# IMU_board_rev2.net
KiCad netlist of a schematic drawn in Altium Designer
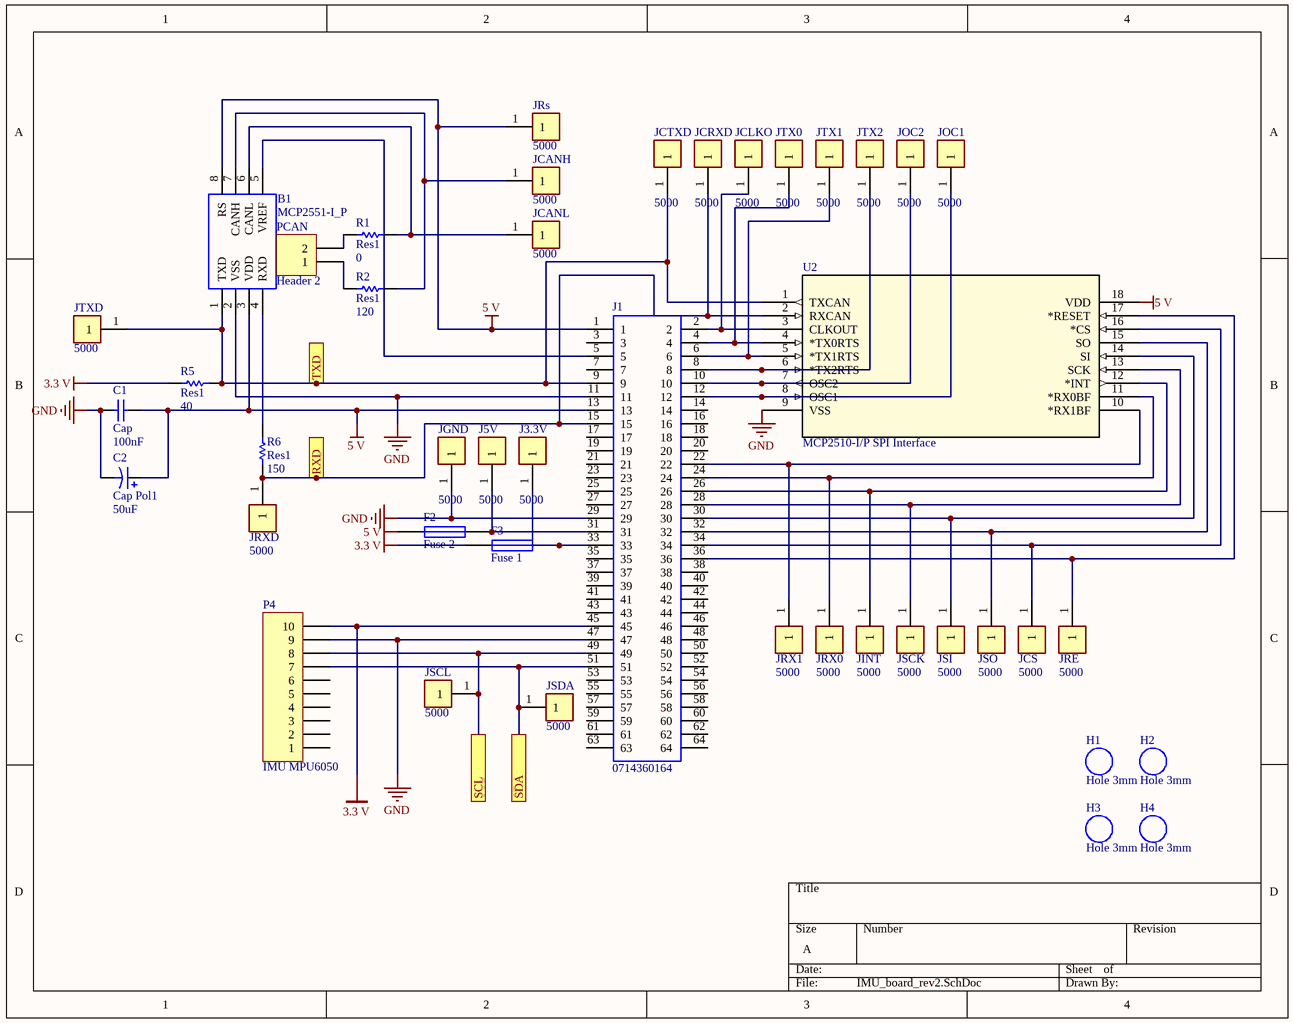
[diagram p0: IMU_board_rev2.SchDoc]

(export (version "E")
  (design (tool "Eeschema 10.0.6"))
  (components
    (comp (ref "B1")
      (value "MCP2551-I_P")
      (footprint "DIP794W56P254L946H432Q8N")
      (fields
        (field (name "MANUFACTURER_PART_NUMBER") "MCP2551-I/P")
        (field (name "MOUSER PART NUMBER") "579-MCP2551-I/P")
      )
      (libsource (lib "MCP2551-I_P") (part "MCP2551-I_P"))
    )
    (comp (ref "C1")
      (value "Cap")
      (footprint "Cap Pol")
      (description "Capacitor")
      (fields (field (name "ALTIUM_VALUE") "100nF") (field (name "PUBLISHER") "Altium Limited"))
      (libsource (lib "Miscellaneous Devices") (part "Cap"))
    )
    (comp (ref "C2")
      (value "Cap Pol1")
      (footprint "Cap Pol")
      (description "Polarized Capacitor (Radial)")
      (fields (field (name "ALTIUM_VALUE") "50uF") (field (name "PUBLISHER") "Altium Limited"))
      (libsource (lib "Miscellaneous Devices") (part "Cap Pol1"))
    )
    (comp (ref "F2")
      (value "Fuse 2")
      (footprint "PIN-W2/E2.8")
      (description "Fuse")
      (fields (field (name "PUBLISHER") "Altium Limited"))
      (libsource (lib "Miscellaneous Devices") (part "Fuse 1"))
    )
    (comp (ref "F3")
      (value "Fuse 1")
      (footprint "PIN-W2/E2.8")
      (description "Fuse")
      (fields (field (name "PUBLISHER") "Altium Limited"))
      (libsource (lib "Miscellaneous Devices") (part "Fuse 1"))
    )
    (comp (ref "H1")
      (value "Hole 3mm")
      (footprint "Hole 3mm")
      (libsource (lib "ECE LIB new") (part "Hole 3mm"))
    )
    (comp (ref "H2")
      (value "Hole 3mm")
      (footprint "Hole 3mm")
      (libsource (lib "ECE LIB new") (part "Hole 3mm"))
    )
    (comp (ref "H3")
      (value "Hole 3mm")
      (footprint "Hole 3mm")
      (libsource (lib "ECE LIB new") (part "Hole 3mm"))
    )
    (comp (ref "H4")
      (value "Hole 3mm")
      (footprint "Hole 3mm")
      (libsource (lib "ECE LIB new") (part "Hole 3mm"))
    )
    (comp (ref "J1")
      (value "0714360164")
      (footprint "0714360164")
      (description "Board to Board & Mezzanine Connectors 1.00MM PLG 02X32P VT SMT")
      (libsource (lib "0714360164") (part "0714360164"))
    )
    (comp (ref "J3.3V")
      (value "5000")
      (footprint "KEYSTONE_5000")
      (fields (field (name "MF") "Keystone"))
      (libsource (lib "5000") (part "5000"))
    )
    (comp (ref "J5V")
      (value "5000")
      (footprint "KEYSTONE_5000")
      (fields (field (name "MF") "Keystone"))
      (libsource (lib "5000") (part "5000"))
    )
    (comp (ref "JCANH")
      (value "5000")
      (footprint "KEYSTONE_5000")
      (fields (field (name "MF") "Keystone"))
      (libsource (lib "") (part "5000_2"))
    )
    (comp (ref "JCANL")
      (value "5000")
      (footprint "KEYSTONE_5000")
      (fields (field (name "MF") "Keystone"))
      (libsource (lib "") (part "5000_2"))
    )
    (comp (ref "JCLKO")
      (value "5000")
      (footprint "KEYSTONE_5000")
      (fields (field (name "MF") "Keystone"))
      (libsource (lib "5000") (part "5000"))
    )
    (comp (ref "JCRXD")
      (value "5000")
      (footprint "KEYSTONE_5000")
      (fields (field (name "MF") "Keystone"))
      (libsource (lib "5000") (part "5000"))
    )
    (comp (ref "JCS")
      (value "5000")
      (footprint "KEYSTONE_5000")
      (fields (field (name "MF") "Keystone"))
      (libsource (lib "") (part "5000_1"))
    )
    (comp (ref "JCTXD")
      (value "5000")
      (footprint "KEYSTONE_5000")
      (fields (field (name "MF") "Keystone"))
      (libsource (lib "5000") (part "5000"))
    )
    (comp (ref "JGND")
      (value "5000")
      (footprint "KEYSTONE_5000")
      (fields (field (name "MF") "Keystone"))
      (libsource (lib "5000") (part "5000"))
    )
    (comp (ref "JINT")
      (value "5000")
      (footprint "KEYSTONE_5000")
      (fields (field (name "MF") "Keystone"))
      (libsource (lib "") (part "5000_1"))
    )
    (comp (ref "JOC1")
      (value "5000")
      (footprint "KEYSTONE_5000")
      (fields (field (name "MF") "Keystone"))
      (libsource (lib "5000") (part "5000"))
    )
    (comp (ref "JOC2")
      (value "5000")
      (footprint "KEYSTONE_5000")
      (fields (field (name "MF") "Keystone"))
      (libsource (lib "5000") (part "5000"))
    )
    (comp (ref "JRE")
      (value "5000")
      (footprint "KEYSTONE_5000")
      (fields (field (name "MF") "Keystone"))
      (libsource (lib "") (part "5000_1"))
    )
    (comp (ref "JRs")
      (value "5000")
      (footprint "KEYSTONE_5000")
      (fields (field (name "MF") "Keystone"))
      (libsource (lib "") (part "5000_2"))
    )
    (comp (ref "JRX0")
      (value "5000")
      (footprint "KEYSTONE_5000")
      (fields (field (name "MF") "Keystone"))
      (libsource (lib "") (part "5000_1"))
    )
    (comp (ref "JRX1")
      (value "5000")
      (footprint "KEYSTONE_5000")
      (fields (field (name "MF") "Keystone"))
      (libsource (lib "") (part "5000_1"))
    )
    (comp (ref "JRXD")
      (value "5000")
      (footprint "KEYSTONE_5000")
      (fields (field (name "MF") "Keystone"))
      (libsource (lib "") (part "5000_1"))
    )
    (comp (ref "JSCK")
      (value "5000")
      (footprint "KEYSTONE_5000")
      (fields (field (name "MF") "Keystone"))
      (libsource (lib "") (part "5000_1"))
    )
    (comp (ref "JSCL")
      (value "5000")
      (footprint "KEYSTONE_5000")
      (fields (field (name "MF") "Keystone"))
      (libsource (lib "") (part "5000_3"))
    )
    (comp (ref "JSDA")
      (value "5000")
      (footprint "KEYSTONE_5000")
      (fields (field (name "MF") "Keystone"))
      (libsource (lib "") (part "5000_2"))
    )
    (comp (ref "JSI")
      (value "5000")
      (footprint "KEYSTONE_5000")
      (fields (field (name "MF") "Keystone"))
      (libsource (lib "") (part "5000_1"))
    )
    (comp (ref "JSO")
      (value "5000")
      (footprint "KEYSTONE_5000")
      (fields (field (name "MF") "Keystone"))
      (libsource (lib "") (part "5000_1"))
    )
    (comp (ref "JTX0")
      (value "5000")
      (footprint "KEYSTONE_5000")
      (fields (field (name "MF") "Keystone"))
      (libsource (lib "5000") (part "5000"))
    )
    (comp (ref "JTX1")
      (value "5000")
      (footprint "KEYSTONE_5000")
      (fields (field (name "MF") "Keystone"))
      (libsource (lib "5000") (part "5000"))
    )
    (comp (ref "JTX2")
      (value "5000")
      (footprint "KEYSTONE_5000")
      (fields (field (name "MF") "Keystone"))
      (libsource (lib "5000") (part "5000"))
    )
    (comp (ref "JTXD")
      (value "5000")
      (footprint "KEYSTONE_5000")
      (fields (field (name "MF") "Keystone"))
      (libsource (lib "") (part "5000_3"))
    )
    (comp (ref "P4")
      (value "IMU MPU6050")
      (footprint "HDR1X10")
      (description "Header, 10-Pin")
      (fields (field (name "PUBLISHER") "Altium Limited"))
      (libsource (lib "Miscellaneous Connectors") (part "Header 10"))
    )
    (comp (ref "PCAN")
      (value "Header 2")
      (footprint "HDR1X2")
      (description "Header, 2-Pin")
      (fields (field (name "PUBLISHER") "Altium Limited"))
      (libsource (lib "Miscellaneous Connectors") (part "Header 2"))
    )
    (comp (ref "R1")
      (value "Res1")
      (footprint "AXIAL-0.3")
      (description "Resistor")
      (fields (field (name "ALTIUM_VALUE") "0") (field (name "PUBLISHER") "Altium Limited"))
      (libsource (lib "Miscellaneous Devices") (part "Res1"))
    )
    (comp (ref "R2")
      (value "Res1")
      (footprint "AXIAL-0.3")
      (description "Resistor")
      (fields (field (name "ALTIUM_VALUE") "120") (field (name "PUBLISHER") "Altium Limited"))
      (libsource (lib "Miscellaneous Devices") (part "Res1"))
    )
    (comp (ref "R5")
      (value "Res1")
      (footprint "AXIAL-0.3")
      (description "Resistor")
      (fields (field (name "ALTIUM_VALUE") "40") (field (name "PUBLISHER") "Altium Limited"))
      (libsource (lib "Miscellaneous Devices") (part "Res1"))
    )
    (comp (ref "R6")
      (value "Res1")
      (footprint "AXIAL-0.3")
      (description "Resistor")
      (fields (field (name "ALTIUM_VALUE") "150") (field (name "PUBLISHER") "Altium Limited"))
      (libsource (lib "Miscellaneous Devices") (part "Res1"))
    )
    (comp (ref "U2")
      (value "MCP2510-I/P SPI Interface")
      (footprint "PDIP18_300MC_MCH")
      (description "No Description Available")
      (fields
        (field (name "MANUFACTURER_PART_NUMBER") "MCP2510-I/P")
        (field (name "COPYRIGHT") "Copyright (C) 2022 Ultra Librarian. All rights reserved.")
      )
      (libsource (lib "MCP2510-I&slash_P") (part "MCP2510-I/P"))
    )
  )
  (nets
    (net (code "1") (name "/RXD") (class "Default")
      (node (ref "J1") (pin "15") (pinfunction "15_15") (pintype "passive"))
      (node (ref "JCRXD") (pin "1") (pinfunction "1_1") (pintype "passive"))
      (node (ref "JRXD") (pin "1") (pinfunction "1_1") (pintype "passive"))
      (node (ref "R6") (pin "2") (pinfunction "2_2") (pintype "passive"))
      (node (ref "U2") (pin "2") (pinfunction "RXCAN_2") (pintype "input"))
    )
    (net (code "2") (name "/SCL") (class "Default")
      (node (ref "J1") (pin "49") (pinfunction "49_49") (pintype "passive"))
      (node (ref "JSCL") (pin "1") (pinfunction "1_1") (pintype "passive"))
      (node (ref "P4") (pin "8") (pinfunction "8_8") (pintype "passive"))
    )
    (net (code "3") (name "/SDA") (class "Default")
      (node (ref "J1") (pin "51") (pinfunction "51_51") (pintype "passive"))
      (node (ref "JSDA") (pin "1") (pinfunction "1_1") (pintype "passive"))
      (node (ref "P4") (pin "7") (pinfunction "7_7") (pintype "passive"))
    )
    (net (code "4") (name "/TXD") (class "Default")
      (node (ref "B1") (pin "1") (pinfunction "TXD_1") (pintype "passive"))
      (node (ref "J1") (pin "9") (pinfunction "9_9") (pintype "passive"))
      (node (ref "JCTXD") (pin "1") (pinfunction "1_1") (pintype "passive"))
      (node (ref "JTXD") (pin "1") (pinfunction "1_1") (pintype "passive"))
      (node (ref "R5") (pin "1") (pinfunction "1_1") (pintype "passive"))
      (node (ref "U2") (pin "1") (pinfunction "TXCAN_1") (pintype "output"))
    )
    (net (code "5") (name "3.3 V") (class "Default")
      (node (ref "F3") (pin "2") (pinfunction "2_2") (pintype "passive"))
      (node (ref "J1") (pin "45") (pinfunction "45_45") (pintype "passive"))
      (node (ref "P4") (pin "10") (pinfunction "10_10") (pintype "passive"))
      (node (ref "R5") (pin "2") (pinfunction "2_2") (pintype "passive"))
    )
    (net (code "6") (name "5 V") (class "Default")
      (node (ref "B1") (pin "3") (pinfunction "VDD_3") (pintype "passive"))
      (node (ref "B1") (pin "8") (pinfunction "RS_8") (pintype "passive"))
      (node (ref "C1") (pin "2") (pinfunction "2_2") (pintype "passive"))
      (node (ref "C2") (pin "1") (pinfunction "1_1") (pintype "passive"))
      (node (ref "F2") (pin "2") (pinfunction "2_2") (pintype "passive"))
      (node (ref "J1") (pin "1") (pinfunction "1_1") (pintype "passive"))
      (node (ref "J1") (pin "13") (pinfunction "13_13") (pintype "passive"))
      (node (ref "JRs") (pin "1") (pinfunction "1_1") (pintype "passive"))
      (node (ref "U2") (pin "18") (pinfunction "VDD_18") (pintype "passive"))
    )
    (net (code "7") (name "GND") (class "Default")
      (node (ref "B1") (pin "2") (pinfunction "VSS_2") (pintype "passive"))
      (node (ref "C1") (pin "1") (pinfunction "1_1") (pintype "passive"))
      (node (ref "C2") (pin "2") (pinfunction "2_2") (pintype "passive"))
      (node (ref "J1") (pin "11") (pinfunction "11_11") (pintype "passive"))
      (node (ref "J1") (pin "29") (pinfunction "29_29") (pintype "passive"))
      (node (ref "J1") (pin "47") (pinfunction "47_47") (pintype "passive"))
      (node (ref "JGND") (pin "1") (pinfunction "1_1") (pintype "passive"))
      (node (ref "P4") (pin "9") (pinfunction "9_9") (pintype "passive"))
      (node (ref "U2") (pin "9") (pinfunction "VSS_9") (pintype "passive"))
    )
    (net (code "8") (name "Net-(B1-CANH)") (class "Default")
      (node (ref "B1") (pin "7") (pinfunction "CANH_7") (pintype "passive"))
      (node (ref "JCANH") (pin "1") (pinfunction "1_1") (pintype "passive"))
      (node (ref "R2") (pin "2") (pinfunction "2_2") (pintype "passive"))
    )
    (net (code "9") (name "Net-(B1-CANL)") (class "Default")
      (node (ref "B1") (pin "6") (pinfunction "CANL_6") (pintype "passive"))
      (node (ref "JCANL") (pin "1") (pinfunction "1_1") (pintype "passive"))
      (node (ref "R1") (pin "2") (pinfunction "2_2") (pintype "passive"))
    )
    (net (code "10") (name "Net-(B1-RXD)") (class "Default")
      (node (ref "B1") (pin "4") (pinfunction "RXD_4") (pintype "passive"))
      (node (ref "R6") (pin "1") (pinfunction "1_1") (pintype "passive"))
    )
    (net (code "11") (name "Net-(B1-VREF)") (class "Default")
      (node (ref "B1") (pin "5") (pinfunction "VREF_5") (pintype "passive"))
      (node (ref "J1") (pin "5") (pinfunction "5_5") (pintype "passive"))
    )
    (net (code "12") (name "Net-(F2-Pad1)") (class "Default")
      (node (ref "F2") (pin "1") (pinfunction "1_1") (pintype "passive"))
      (node (ref "J1") (pin "31") (pinfunction "31_31") (pintype "passive"))
      (node (ref "J5V") (pin "1") (pinfunction "1_1") (pintype "passive"))
    )
    (net (code "13") (name "Net-(F3-Pad1)") (class "Default")
      (node (ref "F3") (pin "1") (pinfunction "1_1") (pintype "passive"))
      (node (ref "J1") (pin "33") (pinfunction "33_33") (pintype "passive"))
      (node (ref "J3.3V") (pin "1") (pinfunction "1_1") (pintype "passive"))
    )
    (net (code "14") (name "Net-(PCAN-Pad1)") (class "Default")
      (node (ref "PCAN") (pin "1") (pinfunction "1_1") (pintype "passive"))
      (node (ref "R2") (pin "1") (pinfunction "1_1") (pintype "passive"))
    )
    (net (code "15") (name "Net-(PCAN-Pad2)") (class "Default")
      (node (ref "PCAN") (pin "2") (pinfunction "2_2") (pintype "passive"))
      (node (ref "R1") (pin "1") (pinfunction "1_1") (pintype "passive"))
    )
    (net (code "16") (name "Net-(U2-*CS)") (class "Default")
      (node (ref "J1") (pin "34") (pinfunction "34_34") (pintype "passive"))
      (node (ref "JCS") (pin "1") (pinfunction "1_1") (pintype "passive"))
      (node (ref "U2") (pin "16") (pinfunction "*CS_16") (pintype "input"))
    )
    (net (code "17") (name "Net-(U2-*INT)") (class "Default")
      (node (ref "J1") (pin "26") (pinfunction "26_26") (pintype "passive"))
      (node (ref "JINT") (pin "1") (pinfunction "1_1") (pintype "passive"))
      (node (ref "U2") (pin "12") (pinfunction "*INT_12") (pintype "output"))
    )
    (net (code "18") (name "Net-(U2-*RESET)") (class "Default")
      (node (ref "J1") (pin "36") (pinfunction "36_36") (pintype "passive"))
      (node (ref "JRE") (pin "1") (pinfunction "1_1") (pintype "passive"))
      (node (ref "U2") (pin "17") (pinfunction "*RESET_17") (pintype "input"))
    )
    (net (code "19") (name "Net-(U2-*RX0BF)") (class "Default")
      (node (ref "J1") (pin "24") (pinfunction "24_24") (pintype "passive"))
      (node (ref "JRX0") (pin "1") (pinfunction "1_1") (pintype "passive"))
      (node (ref "U2") (pin "11") (pinfunction "*RX0BF_11") (pintype "tri_state"))
    )
    (net (code "20") (name "Net-(U2-*RX1BF)") (class "Default")
      (node (ref "J1") (pin "22") (pinfunction "22_22") (pintype "passive"))
      (node (ref "JRX1") (pin "1") (pinfunction "1_1") (pintype "passive"))
      (node (ref "U2") (pin "10") (pinfunction "*RX1BF_10") (pintype "tri_state"))
    )
    (net (code "21") (name "Net-(U2-*TX0RTS)") (class "Default")
      (node (ref "J1") (pin "4") (pinfunction "4_4") (pintype "passive"))
      (node (ref "JTX0") (pin "1") (pinfunction "1_1") (pintype "passive"))
      (node (ref "U2") (pin "4") (pinfunction "*TX0RTS_4") (pintype "input"))
    )
    (net (code "22") (name "Net-(U2-*TX1RTS)") (class "Default")
      (node (ref "J1") (pin "6") (pinfunction "6_6") (pintype "passive"))
      (node (ref "JTX1") (pin "1") (pinfunction "1_1") (pintype "passive"))
      (node (ref "U2") (pin "5") (pinfunction "*TX1RTS_5") (pintype "input"))
    )
    (net (code "23") (name "Net-(U2-*TX2RTS)") (class "Default")
      (node (ref "J1") (pin "8") (pinfunction "8_8") (pintype "passive"))
      (node (ref "JTX2") (pin "1") (pinfunction "1_1") (pintype "passive"))
      (node (ref "U2") (pin "6") (pinfunction "*TX2RTS_6") (pintype "input"))
    )
    (net (code "24") (name "Net-(U2-CLKOUT)") (class "Default")
      (node (ref "J1") (pin "2") (pinfunction "2_2") (pintype "passive"))
      (node (ref "JCLKO") (pin "1") (pinfunction "1_1") (pintype "passive"))
      (node (ref "U2") (pin "3") (pinfunction "CLKOUT_3") (pintype "tri_state"))
    )
    (net (code "25") (name "Net-(U2-OSC1)") (class "Default")
      (node (ref "J1") (pin "12") (pinfunction "12_12") (pintype "passive"))
      (node (ref "JOC1") (pin "1") (pinfunction "1_1") (pintype "passive"))
      (node (ref "U2") (pin "8") (pinfunction "OSC1_8") (pintype "input"))
    )
    (net (code "26") (name "Net-(U2-OSC2)") (class "Default")
      (node (ref "J1") (pin "10") (pinfunction "10_10") (pintype "passive"))
      (node (ref "JOC2") (pin "1") (pinfunction "1_1") (pintype "passive"))
      (node (ref "U2") (pin "7") (pinfunction "OSC2_7") (pintype "output"))
    )
    (net (code "27") (name "Net-(U2-SCK)") (class "Default")
      (node (ref "J1") (pin "28") (pinfunction "28_28") (pintype "passive"))
      (node (ref "JSCK") (pin "1") (pinfunction "1_1") (pintype "passive"))
      (node (ref "U2") (pin "13") (pinfunction "SCK_13") (pintype "input"))
    )
    (net (code "28") (name "Net-(U2-SI)") (class "Default")
      (node (ref "J1") (pin "30") (pinfunction "30_30") (pintype "passive"))
      (node (ref "JSI") (pin "1") (pinfunction "1_1") (pintype "passive"))
      (node (ref "U2") (pin "14") (pinfunction "SI_14") (pintype "input"))
    )
    (net (code "29") (name "Net-(U2-SO)") (class "Default")
      (node (ref "J1") (pin "32") (pinfunction "32_32") (pintype "passive"))
      (node (ref "JSO") (pin "1") (pinfunction "1_1") (pintype "passive"))
      (node (ref "U2") (pin "15") (pinfunction "SO_15") (pintype "tri_state"))
    )
    (net (code "30") (name "unconnected-(J1-Pad3)") (class "Default")
      (node (ref "J1") (pin "3") (pinfunction "3_3") (pintype "passive"))
    )
    (net (code "31") (name "unconnected-(J1-Pad7)") (class "Default")
      (node (ref "J1") (pin "7") (pinfunction "7_7") (pintype "passive"))
    )
    (net (code "32") (name "unconnected-(J1-Pad14)") (class "Default")
      (node (ref "J1") (pin "14") (pinfunction "14_14") (pintype "passive"))
    )
    (net (code "33") (name "unconnected-(J1-Pad16)") (class "Default")
      (node (ref "J1") (pin "16") (pinfunction "16_16") (pintype "passive"))
    )
    (net (code "34") (name "unconnected-(J1-Pad17)") (class "Default")
      (node (ref "J1") (pin "17") (pinfunction "17_17") (pintype "passive"))
    )
    (net (code "35") (name "unconnected-(J1-Pad18)") (class "Default")
      (node (ref "J1") (pin "18") (pinfunction "18_18") (pintype "passive"))
    )
    (net (code "36") (name "unconnected-(J1-Pad19)") (class "Default")
      (node (ref "J1") (pin "19") (pinfunction "19_19") (pintype "passive"))
    )
    (net (code "37") (name "unconnected-(J1-Pad20)") (class "Default")
      (node (ref "J1") (pin "20") (pinfunction "20_20") (pintype "passive"))
    )
    (net (code "38") (name "unconnected-(J1-Pad21)") (class "Default")
      (node (ref "J1") (pin "21") (pinfunction "21_21") (pintype "passive"))
    )
    (net (code "39") (name "unconnected-(J1-Pad23)") (class "Default")
      (node (ref "J1") (pin "23") (pinfunction "23_23") (pintype "passive"))
    )
    (net (code "40") (name "unconnected-(J1-Pad25)") (class "Default")
      (node (ref "J1") (pin "25") (pinfunction "25_25") (pintype "passive"))
    )
    (net (code "41") (name "unconnected-(J1-Pad27)") (class "Default")
      (node (ref "J1") (pin "27") (pinfunction "27_27") (pintype "passive"))
    )
    (net (code "42") (name "unconnected-(J1-Pad35)") (class "Default")
      (node (ref "J1") (pin "35") (pinfunction "35_35") (pintype "passive"))
    )
    (net (code "43") (name "unconnected-(J1-Pad37)") (class "Default")
      (node (ref "J1") (pin "37") (pinfunction "37_37") (pintype "passive"))
    )
    (net (code "44") (name "unconnected-(J1-Pad38)") (class "Default")
      (node (ref "J1") (pin "38") (pinfunction "38_38") (pintype "passive"))
    )
    (net (code "45") (name "unconnected-(J1-Pad39)") (class "Default")
      (node (ref "J1") (pin "39") (pinfunction "39_39") (pintype "passive"))
    )
    (net (code "46") (name "unconnected-(J1-Pad40)") (class "Default")
      (node (ref "J1") (pin "40") (pinfunction "40_40") (pintype "passive"))
    )
    (net (code "47") (name "unconnected-(J1-Pad41)") (class "Default")
      (node (ref "J1") (pin "41") (pinfunction "41_41") (pintype "passive"))
    )
    (net (code "48") (name "unconnected-(J1-Pad42)") (class "Default")
      (node (ref "J1") (pin "42") (pinfunction "42_42") (pintype "passive"))
    )
    (net (code "49") (name "unconnected-(J1-Pad43)") (class "Default")
      (node (ref "J1") (pin "43") (pinfunction "43_43") (pintype "passive"))
    )
    (net (code "50") (name "unconnected-(J1-Pad44)") (class "Default")
      (node (ref "J1") (pin "44") (pinfunction "44_44") (pintype "passive"))
    )
    (net (code "51") (name "unconnected-(J1-Pad46)") (class "Default")
      (node (ref "J1") (pin "46") (pinfunction "46_46") (pintype "passive"))
    )
    (net (code "52") (name "unconnected-(J1-Pad48)") (class "Default")
      (node (ref "J1") (pin "48") (pinfunction "48_48") (pintype "passive"))
    )
    (net (code "53") (name "unconnected-(J1-Pad50)") (class "Default")
      (node (ref "J1") (pin "50") (pinfunction "50_50") (pintype "passive"))
    )
    (net (code "54") (name "unconnected-(J1-Pad52)") (class "Default")
      (node (ref "J1") (pin "52") (pinfunction "52_52") (pintype "passive"))
    )
    (net (code "55") (name "unconnected-(J1-Pad53)") (class "Default")
      (node (ref "J1") (pin "53") (pinfunction "53_53") (pintype "passive"))
    )
    (net (code "56") (name "unconnected-(J1-Pad54)") (class "Default")
      (node (ref "J1") (pin "54") (pinfunction "54_54") (pintype "passive"))
    )
    (net (code "57") (name "unconnected-(J1-Pad55)") (class "Default")
      (node (ref "J1") (pin "55") (pinfunction "55_55") (pintype "passive"))
    )
    (net (code "58") (name "unconnected-(J1-Pad56)") (class "Default")
      (node (ref "J1") (pin "56") (pinfunction "56_56") (pintype "passive"))
    )
    (net (code "59") (name "unconnected-(J1-Pad57)") (class "Default")
      (node (ref "J1") (pin "57") (pinfunction "57_57") (pintype "passive"))
    )
    (net (code "60") (name "unconnected-(J1-Pad58)") (class "Default")
      (node (ref "J1") (pin "58") (pinfunction "58_58") (pintype "passive"))
    )
    (net (code "61") (name "unconnected-(J1-Pad59)") (class "Default")
      (node (ref "J1") (pin "59") (pinfunction "59_59") (pintype "passive"))
    )
    (net (code "62") (name "unconnected-(J1-Pad60)") (class "Default")
      (node (ref "J1") (pin "60") (pinfunction "60_60") (pintype "passive"))
    )
    (net (code "63") (name "unconnected-(J1-Pad61)") (class "Default")
      (node (ref "J1") (pin "61") (pinfunction "61_61") (pintype "passive"))
    )
    (net (code "64") (name "unconnected-(J1-Pad62)") (class "Default")
      (node (ref "J1") (pin "62") (pinfunction "62_62") (pintype "passive"))
    )
    (net (code "65") (name "unconnected-(J1-Pad63)") (class "Default")
      (node (ref "J1") (pin "63") (pinfunction "63_63") (pintype "passive"))
    )
    (net (code "66") (name "unconnected-(J1-Pad64)") (class "Default")
      (node (ref "J1") (pin "64") (pinfunction "64_64") (pintype "passive"))
    )
    (net (code "67") (name "unconnected-(P4-Pad1)") (class "Default")
      (node (ref "P4") (pin "1") (pinfunction "1_1") (pintype "passive"))
    )
    (net (code "68") (name "unconnected-(P4-Pad2)") (class "Default")
      (node (ref "P4") (pin "2") (pinfunction "2_2") (pintype "passive"))
    )
    (net (code "69") (name "unconnected-(P4-Pad3)") (class "Default")
      (node (ref "P4") (pin "3") (pinfunction "3_3") (pintype "passive"))
    )
    (net (code "70") (name "unconnected-(P4-Pad4)") (class "Default")
      (node (ref "P4") (pin "4") (pinfunction "4_4") (pintype "passive"))
    )
    (net (code "71") (name "unconnected-(P4-Pad5)") (class "Default")
      (node (ref "P4") (pin "5") (pinfunction "5_5") (pintype "passive"))
    )
    (net (code "72") (name "unconnected-(P4-Pad6)") (class "Default")
      (node (ref "P4") (pin "6") (pinfunction "6_6") (pintype "passive"))
    )
  )
)
